# MUDE_-_Rev_B.net
KiCad netlist of a schematic drawn in EAGLE
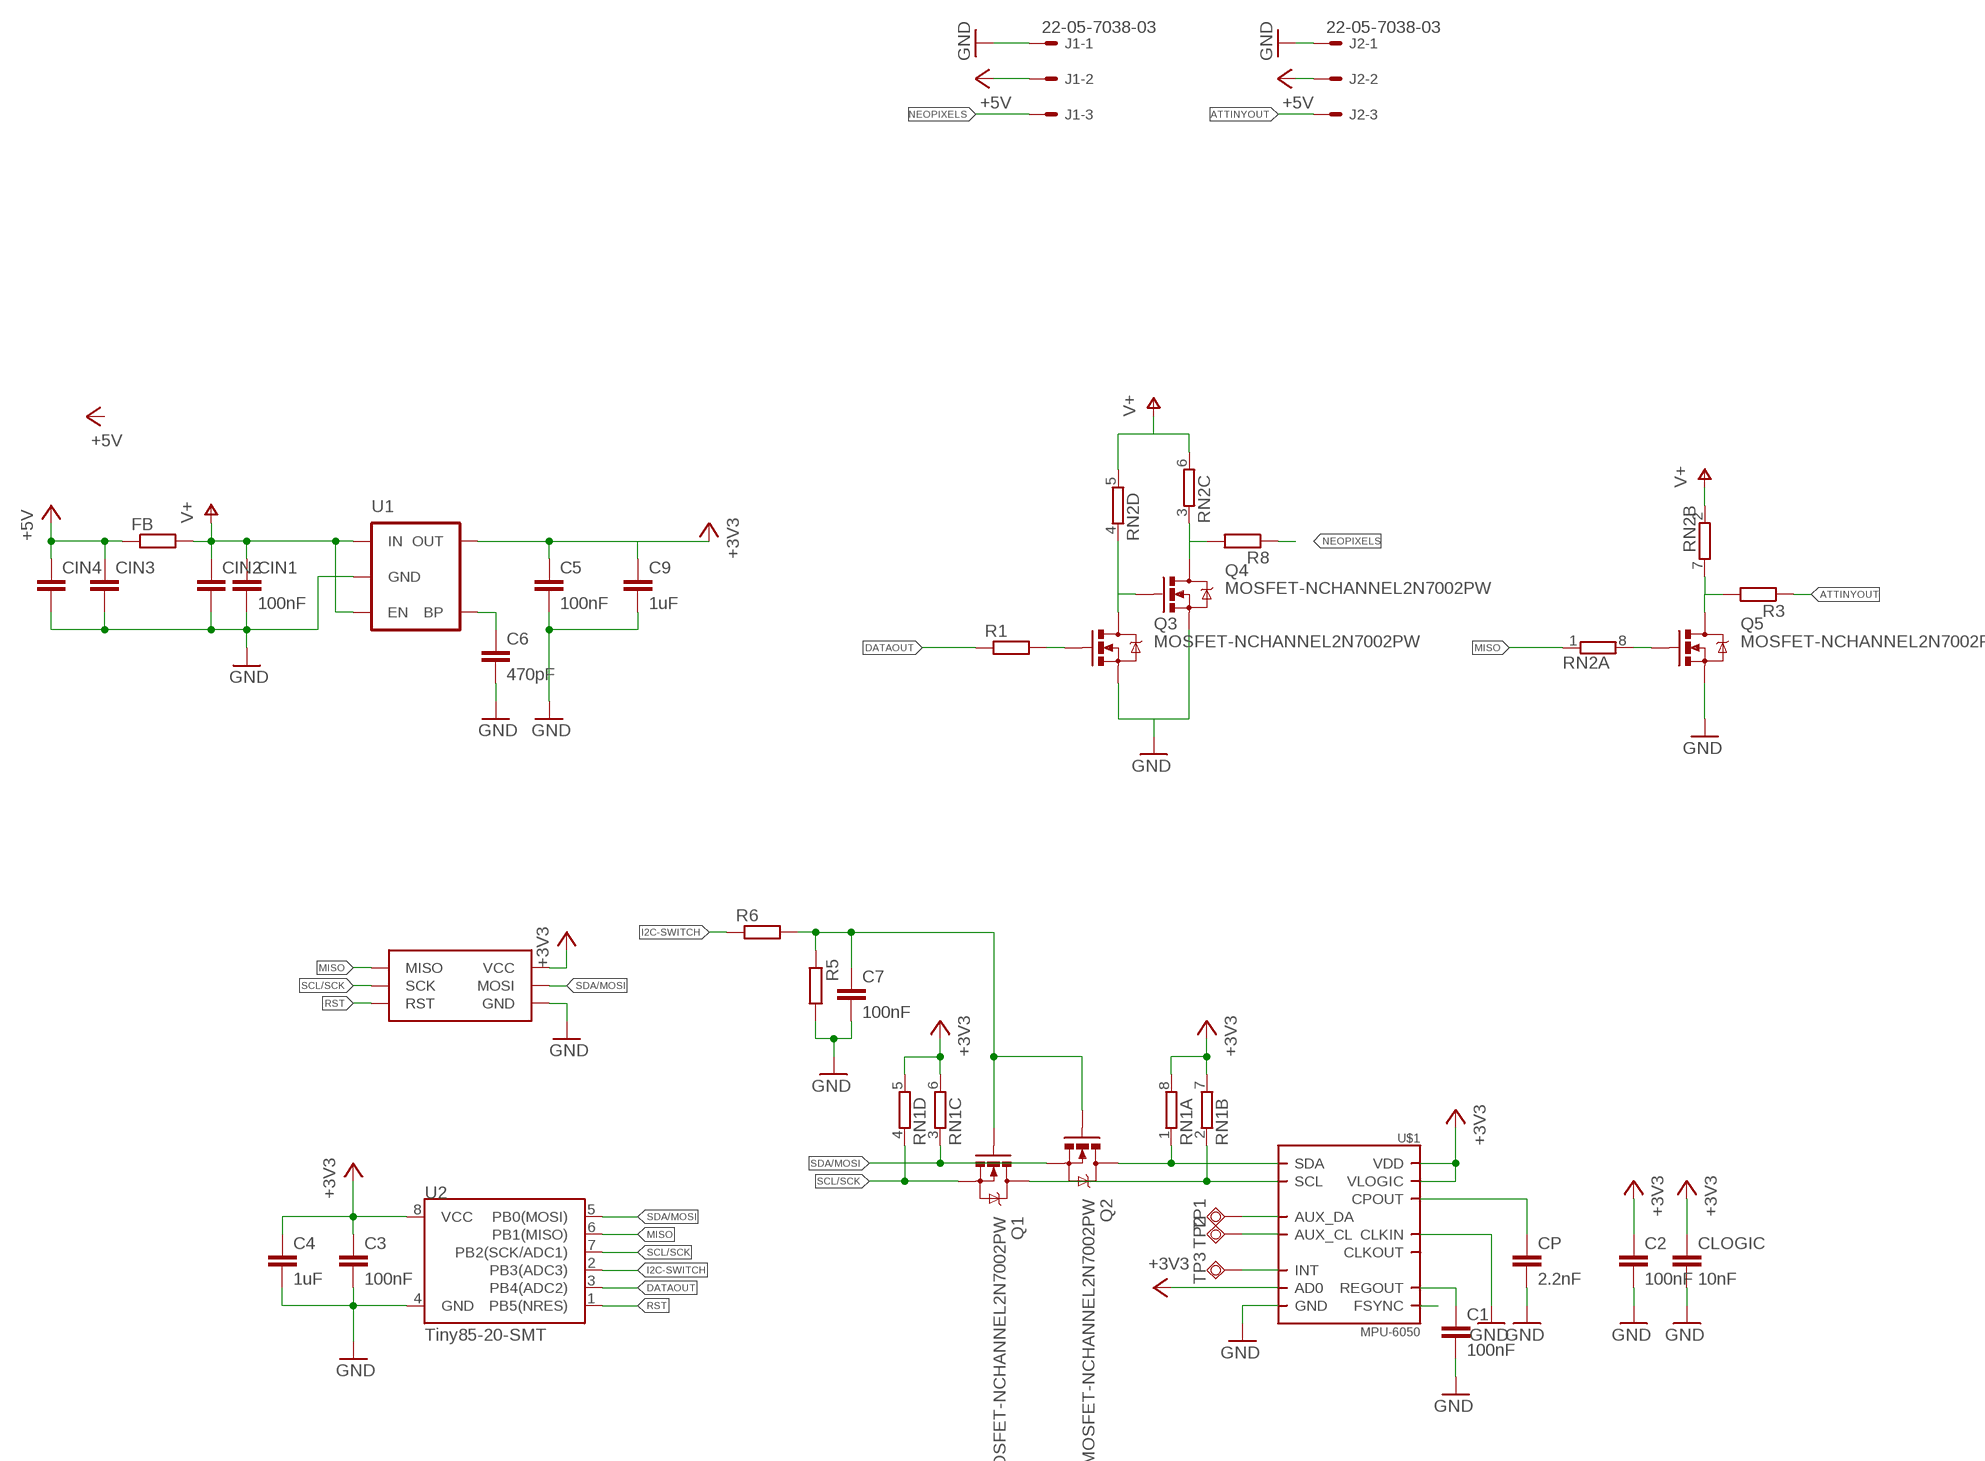
[diagram p0: schematic, sheet 1]

(export (version "E")
  (design (tool "Eeschema 10.0.6"))
  (components
    (comp (ref "C1")
      (value "100nF")
      (footprint "eagle-import:C0603")
      (libsource (lib "eagle-import") (part "C-EUC0603"))
    )
    (comp (ref "C2")
      (value "100nF")
      (footprint "eagle-import:C0603")
      (libsource (lib "eagle-import") (part "C-EUC0603"))
    )
    (comp (ref "C3")
      (value "100nF")
      (footprint "eagle-import:C0603")
      (libsource (lib "eagle-import") (part "C-EUC0603"))
    )
    (comp (ref "C4")
      (value "1uF")
      (footprint "eagle-import:C0603")
      (libsource (lib "eagle-import") (part "C-EUC0603"))
    )
    (comp (ref "C5")
      (value "100nF")
      (footprint "eagle-import:C0805")
      (libsource (lib "eagle-import") (part "C-EUC0805"))
    )
    (comp (ref "C6")
      (value "470pF")
      (footprint "eagle-import:C0603")
      (libsource (lib "eagle-import") (part "C-EUC0603"))
    )
    (comp (ref "C7")
      (value "100nF")
      (footprint "eagle-import:C0603")
      (libsource (lib "eagle-import") (part "C-EUC0603"))
    )
    (comp (ref "C9")
      (value "1uF")
      (footprint "eagle-import:C0603")
      (libsource (lib "eagle-import") (part "C-EUC0603"))
    )
    (comp (ref "CIN1")
      (value "100nF")
      (footprint "eagle-import:C0603")
      (libsource (lib "eagle-import") (part "C-EUC0603"))
    )
    (comp (ref "CIN2")
      (value "C-EUC0805")
      (footprint "eagle-import:C0805")
      (libsource (lib "eagle-import") (part "C-EUC0805"))
    )
    (comp (ref "CIN3")
      (value "C-EUC0805")
      (footprint "eagle-import:C0805")
      (libsource (lib "eagle-import") (part "C-EUC0805"))
    )
    (comp (ref "CIN4")
      (value "C-EUC0805")
      (footprint "eagle-import:C0805")
      (libsource (lib "eagle-import") (part "C-EUC0805"))
    )
    (comp (ref "CLOGIC")
      (value "10nF")
      (footprint "eagle-import:C0603")
      (libsource (lib "eagle-import") (part "C-EUC0603"))
    )
    (comp (ref "CP")
      (value "2.2nF")
      (footprint "eagle-import:C0603")
      (libsource (lib "eagle-import") (part "C-EUC0603"))
    )
    (comp (ref "FB")
      (value "R-EU_R0603")
      (footprint "eagle-import:R0603")
      (libsource (lib "eagle-import") (part "R-EU_R0603"))
    )
    (comp (ref "J1")
      (value "22-05-7038-03")
      (footprint "eagle-import:7395-03")
      (libsource (lib "eagle-import") (part "22-?-0305-7038"))
    )
    (comp (ref "J2")
      (value "22-05-7038-03")
      (footprint "eagle-import:7395-03")
      (libsource (lib "eagle-import") (part "22-?-0305-7038"))
    )
    (comp (ref "Q1")
      (value "MOSFET-NCHANNEL2N7002PW")
      (footprint "eagle-import:SOT323")
      (libsource (lib "eagle-import") (part "MOSFET-NCHANNEL2N7002PW"))
    )
    (comp (ref "Q2")
      (value "MOSFET-NCHANNEL2N7002PW")
      (footprint "eagle-import:SOT323")
      (libsource (lib "eagle-import") (part "MOSFET-NCHANNEL2N7002PW"))
    )
    (comp (ref "Q3")
      (value "MOSFET-NCHANNEL2N7002PW")
      (footprint "eagle-import:SOT323")
      (libsource (lib "eagle-import") (part "MOSFET-NCHANNEL2N7002PW"))
    )
    (comp (ref "Q4")
      (value "MOSFET-NCHANNEL2N7002PW")
      (footprint "eagle-import:SOT323")
      (libsource (lib "eagle-import") (part "MOSFET-NCHANNEL2N7002PW"))
    )
    (comp (ref "Q5")
      (value "MOSFET-NCHANNEL2N7002PW")
      (footprint "eagle-import:SOT323")
      (libsource (lib "eagle-import") (part "MOSFET-NCHANNEL2N7002PW"))
    )
    (comp (ref "R1")
      (value "R-EU_R0603")
      (footprint "eagle-import:R0603")
      (libsource (lib "eagle-import") (part "R-EU_R0603"))
    )
    (comp (ref "R3")
      (value "R-EU_R0603")
      (footprint "eagle-import:R0603")
      (libsource (lib "eagle-import") (part "R-EU_R0603"))
    )
    (comp (ref "R5")
      (value "R-EU_R0603")
      (footprint "eagle-import:R0603")
      (libsource (lib "eagle-import") (part "R-EU_R0603"))
    )
    (comp (ref "R6")
      (value "R-EU_R0603")
      (footprint "eagle-import:R0603")
      (libsource (lib "eagle-import") (part "R-EU_R0603"))
    )
    (comp (ref "R8")
      (value "R-EU_R0603")
      (footprint "eagle-import:R0603")
      (libsource (lib "eagle-import") (part "R-EU_R0603"))
    )
    (comp (ref "RN1")
      (value "4R-N0603-ARV")
      (footprint "eagle-import:0603-ARV")
      (libsource (lib "eagle-import") (part "4R-N0603-ARV"))
    )
    (comp (ref "RN2")
      (value "4R-N0603-ARV")
      (footprint "eagle-import:0603-ARV")
      (libsource (lib "eagle-import") (part "4R-N0603-ARV"))
    )
    (comp (ref "TP1")
      (value "TPSQTP10R")
      (footprint "eagle-import:TP10R")
      (libsource (lib "eagle-import") (part "TPSQTP10R"))
    )
    (comp (ref "TP2")
      (value "TPSQTP10R")
      (footprint "eagle-import:TP10R")
      (libsource (lib "eagle-import") (part "TPSQTP10R"))
    )
    (comp (ref "TP3")
      (value "TPSQTP10R")
      (footprint "eagle-import:TP10R")
      (libsource (lib "eagle-import") (part "TPSQTP10R"))
    )
    (comp (ref "U$1")
      (value "MPU-6050")
      (footprint "eagle-import:QFN.24.4X4")
      (libsource (lib "eagle-import") (part "MPU-6050"))
    )
    (comp (ref "U$3")
      (value "ISP_POGOISP_LHOLE")
      (footprint "eagle-import:ISP_POGO_LHOLE")
      (libsource (lib "eagle-import") (part "ISP_POGOISP_LHOLE"))
    )
    (comp (ref "U1")
      (value "MIC52053.3V")
      (footprint "eagle-import:SOT23-5")
      (libsource (lib "eagle-import") (part "MIC52053.3V"))
    )
    (comp (ref "U2")
      (value "Tiny85-20-SMT")
      (footprint "eagle-import:SO08-EIAJ")
      (libsource (lib "eagle-import") (part "ATTINY45TINY85-20-SMT"))
    )
  )
  (nets
    (net (code "1") (name "+3V3") (class "Default")
      (node (ref "C2") (pin "1") (pinfunction "1_1") (pintype "passive"))
      (node (ref "C3") (pin "1") (pinfunction "1_1") (pintype "passive"))
      (node (ref "C4") (pin "1") (pinfunction "1_1") (pintype "passive"))
      (node (ref "C5") (pin "1") (pinfunction "1_1") (pintype "passive"))
      (node (ref "C9") (pin "1") (pinfunction "1_1") (pintype "passive"))
      (node (ref "CLOGIC") (pin "1") (pinfunction "1_1") (pintype "passive"))
      (node (ref "RN1") (pin "5") (pinfunction "2_5") (pintype "passive"))
      (node (ref "RN1") (pin "6") (pinfunction "2_6") (pintype "passive"))
      (node (ref "RN1") (pin "7") (pinfunction "2_7") (pintype "passive"))
      (node (ref "RN1") (pin "8") (pinfunction "2_8") (pintype "passive"))
      (node (ref "U$1") (pin "13") (pinfunction "VDD_13") (pintype "bidirectional"))
      (node (ref "U$1") (pin "8") (pinfunction "VLOGIC_8") (pintype "bidirectional"))
      (node (ref "U$1") (pin "9") (pinfunction "AD0_9") (pintype "bidirectional"))
      (node (ref "U$3") (pin "VCC") (pinfunction "VCC_VCC") (pintype "bidirectional"))
      (node (ref "U1") (pin "5") (pinfunction "OUT_5") (pintype "passive"))
      (node (ref "U2") (pin "8") (pinfunction "VCC_8") (pintype "bidirectional"))
    )
    (net (code "2") (name "+5V") (class "Default")
      (node (ref "CIN3") (pin "1") (pinfunction "1_1") (pintype "passive"))
      (node (ref "CIN4") (pin "1") (pinfunction "1_1") (pintype "passive"))
      (node (ref "FB") (pin "1") (pinfunction "1_1") (pintype "passive"))
      (node (ref "J1") (pin "2") (pinfunction "S_2") (pintype "passive"))
      (node (ref "J2") (pin "2") (pinfunction "S_2") (pintype "passive"))
    )
    (net (code "3") (name "ATTINYOUT") (class "Default")
      (node (ref "J2") (pin "3") (pinfunction "S_3") (pintype "passive"))
      (node (ref "R3") (pin "1") (pinfunction "1_1") (pintype "passive"))
    )
    (net (code "4") (name "DATAOUT") (class "Default")
      (node (ref "R1") (pin "1") (pinfunction "1_1") (pintype "passive"))
      (node (ref "U2") (pin "3") (pinfunction "PB4(ADC2)_3") (pintype "bidirectional"))
    )
    (net (code "5") (name "GND") (class "Default")
      (node (ref "C1") (pin "2") (pinfunction "2_2") (pintype "passive"))
      (node (ref "C2") (pin "2") (pinfunction "2_2") (pintype "passive"))
      (node (ref "C3") (pin "2") (pinfunction "2_2") (pintype "passive"))
      (node (ref "C4") (pin "2") (pinfunction "2_2") (pintype "passive"))
      (node (ref "C5") (pin "2") (pinfunction "2_2") (pintype "passive"))
      (node (ref "C6") (pin "2") (pinfunction "2_2") (pintype "passive"))
      (node (ref "C7") (pin "2") (pinfunction "2_2") (pintype "passive"))
      (node (ref "C9") (pin "2") (pinfunction "2_2") (pintype "passive"))
      (node (ref "CIN1") (pin "2") (pinfunction "2_2") (pintype "passive"))
      (node (ref "CIN2") (pin "2") (pinfunction "2_2") (pintype "passive"))
      (node (ref "CIN3") (pin "2") (pinfunction "2_2") (pintype "passive"))
      (node (ref "CIN4") (pin "2") (pinfunction "2_2") (pintype "passive"))
      (node (ref "CLOGIC") (pin "2") (pinfunction "2_2") (pintype "passive"))
      (node (ref "CP") (pin "2") (pinfunction "2_2") (pintype "passive"))
      (node (ref "J1") (pin "1") (pinfunction "S_1") (pintype "passive"))
      (node (ref "J2") (pin "1") (pinfunction "S_1") (pintype "passive"))
      (node (ref "Q3") (pin "2") (pinfunction "S_2") (pintype "passive"))
      (node (ref "Q4") (pin "2") (pinfunction "S_2") (pintype "passive"))
      (node (ref "Q5") (pin "2") (pinfunction "S_2") (pintype "passive"))
      (node (ref "R5") (pin "2") (pinfunction "2_2") (pintype "passive"))
      (node (ref "U$1") (pin "1") (pinfunction "CLKIN_1") (pintype "bidirectional"))
      (node (ref "U$1") (pin "18") (pinfunction "GND_18") (pintype "bidirectional"))
      (node (ref "U$3") (pin "GND") (pinfunction "GND_GND") (pintype "bidirectional"))
      (node (ref "U1") (pin "2") (pinfunction "GND_2") (pintype "input"))
      (node (ref "U2") (pin "4") (pinfunction "GND_4") (pintype "bidirectional"))
    )
    (net (code "6") (name "I2C-SWITCH") (class "Default")
      (node (ref "R6") (pin "1") (pinfunction "1_1") (pintype "passive"))
      (node (ref "U2") (pin "2") (pinfunction "PB3(ADC3)_2") (pintype "bidirectional"))
    )
    (net (code "7") (name "MISO") (class "Default")
      (node (ref "RN2") (pin "1") (pinfunction "1_1") (pintype "passive"))
      (node (ref "U$3") (pin "MISO") (pinfunction "MISO_MISO") (pintype "bidirectional"))
      (node (ref "U2") (pin "6") (pinfunction "PB1(MISO)_6") (pintype "bidirectional"))
    )
    (net (code "8") (name "NEOPIXELS") (class "Default")
      (node (ref "J1") (pin "3") (pinfunction "S_3") (pintype "passive"))
      (node (ref "R8") (pin "1") (pinfunction "1_1") (pintype "passive"))
    )
    (net (code "9") (name "Net-(Q1-D)") (class "Default")
      (node (ref "Q1") (pin "3") (pinfunction "D_3") (pintype "passive"))
      (node (ref "RN1") (pin "2") (pinfunction "1_2") (pintype "passive"))
      (node (ref "U$1") (pin "23") (pinfunction "SCL_23") (pintype "bidirectional"))
    )
    (net (code "10") (name "Net-(Q1-G)") (class "Default")
      (node (ref "C7") (pin "1") (pinfunction "1_1") (pintype "passive"))
      (node (ref "Q1") (pin "1") (pinfunction "G_1") (pintype "passive"))
      (node (ref "Q2") (pin "1") (pinfunction "G_1") (pintype "passive"))
      (node (ref "R5") (pin "1") (pinfunction "1_1") (pintype "passive"))
      (node (ref "R6") (pin "2") (pinfunction "2_2") (pintype "passive"))
    )
    (net (code "11") (name "Net-(Q2-D)") (class "Default")
      (node (ref "Q2") (pin "3") (pinfunction "D_3") (pintype "passive"))
      (node (ref "RN1") (pin "1") (pinfunction "1_1") (pintype "passive"))
      (node (ref "U$1") (pin "24") (pinfunction "SDA_24") (pintype "bidirectional"))
    )
    (net (code "12") (name "Net-(Q3-D)") (class "Default")
      (node (ref "Q3") (pin "3") (pinfunction "D_3") (pintype "passive"))
      (node (ref "Q4") (pin "1") (pinfunction "G_1") (pintype "passive"))
      (node (ref "RN2") (pin "4") (pinfunction "1_4") (pintype "passive"))
    )
    (net (code "13") (name "Net-(Q3-G)") (class "Default")
      (node (ref "Q3") (pin "1") (pinfunction "G_1") (pintype "passive"))
      (node (ref "R1") (pin "2") (pinfunction "2_2") (pintype "passive"))
    )
    (net (code "14") (name "Net-(Q4-D)") (class "Default")
      (node (ref "Q4") (pin "3") (pinfunction "D_3") (pintype "passive"))
      (node (ref "R8") (pin "2") (pinfunction "2_2") (pintype "passive"))
      (node (ref "RN2") (pin "3") (pinfunction "1_3") (pintype "passive"))
    )
    (net (code "15") (name "Net-(Q5-D)") (class "Default")
      (node (ref "Q5") (pin "3") (pinfunction "D_3") (pintype "passive"))
      (node (ref "R3") (pin "2") (pinfunction "2_2") (pintype "passive"))
      (node (ref "RN2") (pin "7") (pinfunction "2_7") (pintype "passive"))
    )
    (net (code "16") (name "Net-(Q5-G)") (class "Default")
      (node (ref "Q5") (pin "1") (pinfunction "G_1") (pintype "passive"))
      (node (ref "RN2") (pin "8") (pinfunction "2_8") (pintype "passive"))
    )
    (net (code "17") (name "Net-(U$1-AUX_CL)") (class "Default")
      (node (ref "TP2") (pin "TP") (pinfunction "TP_TP") (pintype "input"))
      (node (ref "U$1") (pin "7") (pinfunction "AUX_CL_7") (pintype "bidirectional"))
    )
    (net (code "18") (name "Net-(U$1-AUX_DA)") (class "Default")
      (node (ref "TP1") (pin "TP") (pinfunction "TP_TP") (pintype "input"))
      (node (ref "U$1") (pin "6") (pinfunction "AUX_DA_6") (pintype "bidirectional"))
    )
    (net (code "19") (name "Net-(U$1-CPOUT)") (class "Default")
      (node (ref "CP") (pin "1") (pinfunction "1_1") (pintype "passive"))
      (node (ref "U$1") (pin "20") (pinfunction "CPOUT_20") (pintype "bidirectional"))
    )
    (net (code "20") (name "Net-(U$1-INT)") (class "Default")
      (node (ref "TP3") (pin "TP") (pinfunction "TP_TP") (pintype "input"))
      (node (ref "U$1") (pin "12") (pinfunction "INT_12") (pintype "bidirectional"))
    )
    (net (code "21") (name "Net-(U$1-REGOUT)") (class "Default")
      (node (ref "C1") (pin "1") (pinfunction "1_1") (pintype "passive"))
      (node (ref "U$1") (pin "10") (pinfunction "REGOUT_10") (pintype "bidirectional"))
    )
    (net (code "22") (name "Net-(U1-BP)") (class "Default")
      (node (ref "C6") (pin "1") (pinfunction "1_1") (pintype "passive"))
      (node (ref "U1") (pin "4") (pinfunction "BP_4") (pintype "input"))
    )
    (net (code "23") (name "RST") (class "Default")
      (node (ref "U$3") (pin "RST") (pinfunction "RST_RST") (pintype "bidirectional"))
      (node (ref "U2") (pin "1") (pinfunction "PB5(NRES)_1") (pintype "bidirectional"))
    )
    (net (code "24") (name "SCL{slash}SCK") (class "Default")
      (node (ref "Q1") (pin "2") (pinfunction "S_2") (pintype "passive"))
      (node (ref "RN1") (pin "4") (pinfunction "1_4") (pintype "passive"))
      (node (ref "U$3") (pin "SCK") (pinfunction "SCK_SCK") (pintype "bidirectional"))
      (node (ref "U2") (pin "7") (pinfunction "PB2(SCK/ADC1)_7") (pintype "bidirectional"))
    )
    (net (code "25") (name "SDA{slash}MOSI") (class "Default")
      (node (ref "Q2") (pin "2") (pinfunction "S_2") (pintype "passive"))
      (node (ref "RN1") (pin "3") (pinfunction "1_3") (pintype "passive"))
      (node (ref "U$3") (pin "MOSI") (pinfunction "MOSI_MOSI") (pintype "bidirectional"))
      (node (ref "U2") (pin "5") (pinfunction "PB0(MOSI)_5") (pintype "bidirectional"))
    )
    (net (code "26") (name "V+") (class "Default")
      (node (ref "CIN1") (pin "1") (pinfunction "1_1") (pintype "passive"))
      (node (ref "CIN2") (pin "1") (pinfunction "1_1") (pintype "passive"))
      (node (ref "FB") (pin "2") (pinfunction "2_2") (pintype "passive"))
      (node (ref "RN2") (pin "2") (pinfunction "1_2") (pintype "passive"))
      (node (ref "RN2") (pin "5") (pinfunction "2_5") (pintype "passive"))
      (node (ref "RN2") (pin "6") (pinfunction "2_6") (pintype "passive"))
      (node (ref "U1") (pin "1") (pinfunction "IN_1") (pintype "input"))
      (node (ref "U1") (pin "3") (pinfunction "EN_3") (pintype "input"))
    )
    (net (code "27") (name "unconnected-(U$1-CLKOUT-Pad22)") (class "Default")
      (node (ref "U$1") (pin "22") (pinfunction "CLKOUT_22") (pintype "bidirectional"))
    )
    (net (code "28") (name "unconnected-(U$1-FSYNC-Pad11)") (class "Default")
      (node (ref "U$1") (pin "11") (pinfunction "FSYNC_11") (pintype "bidirectional"))
    )
  )
)
